# ESP-Light-Controller_2020-12-21_12-57-52.net
KiCad netlist of a schematic drawn in EasyEDA
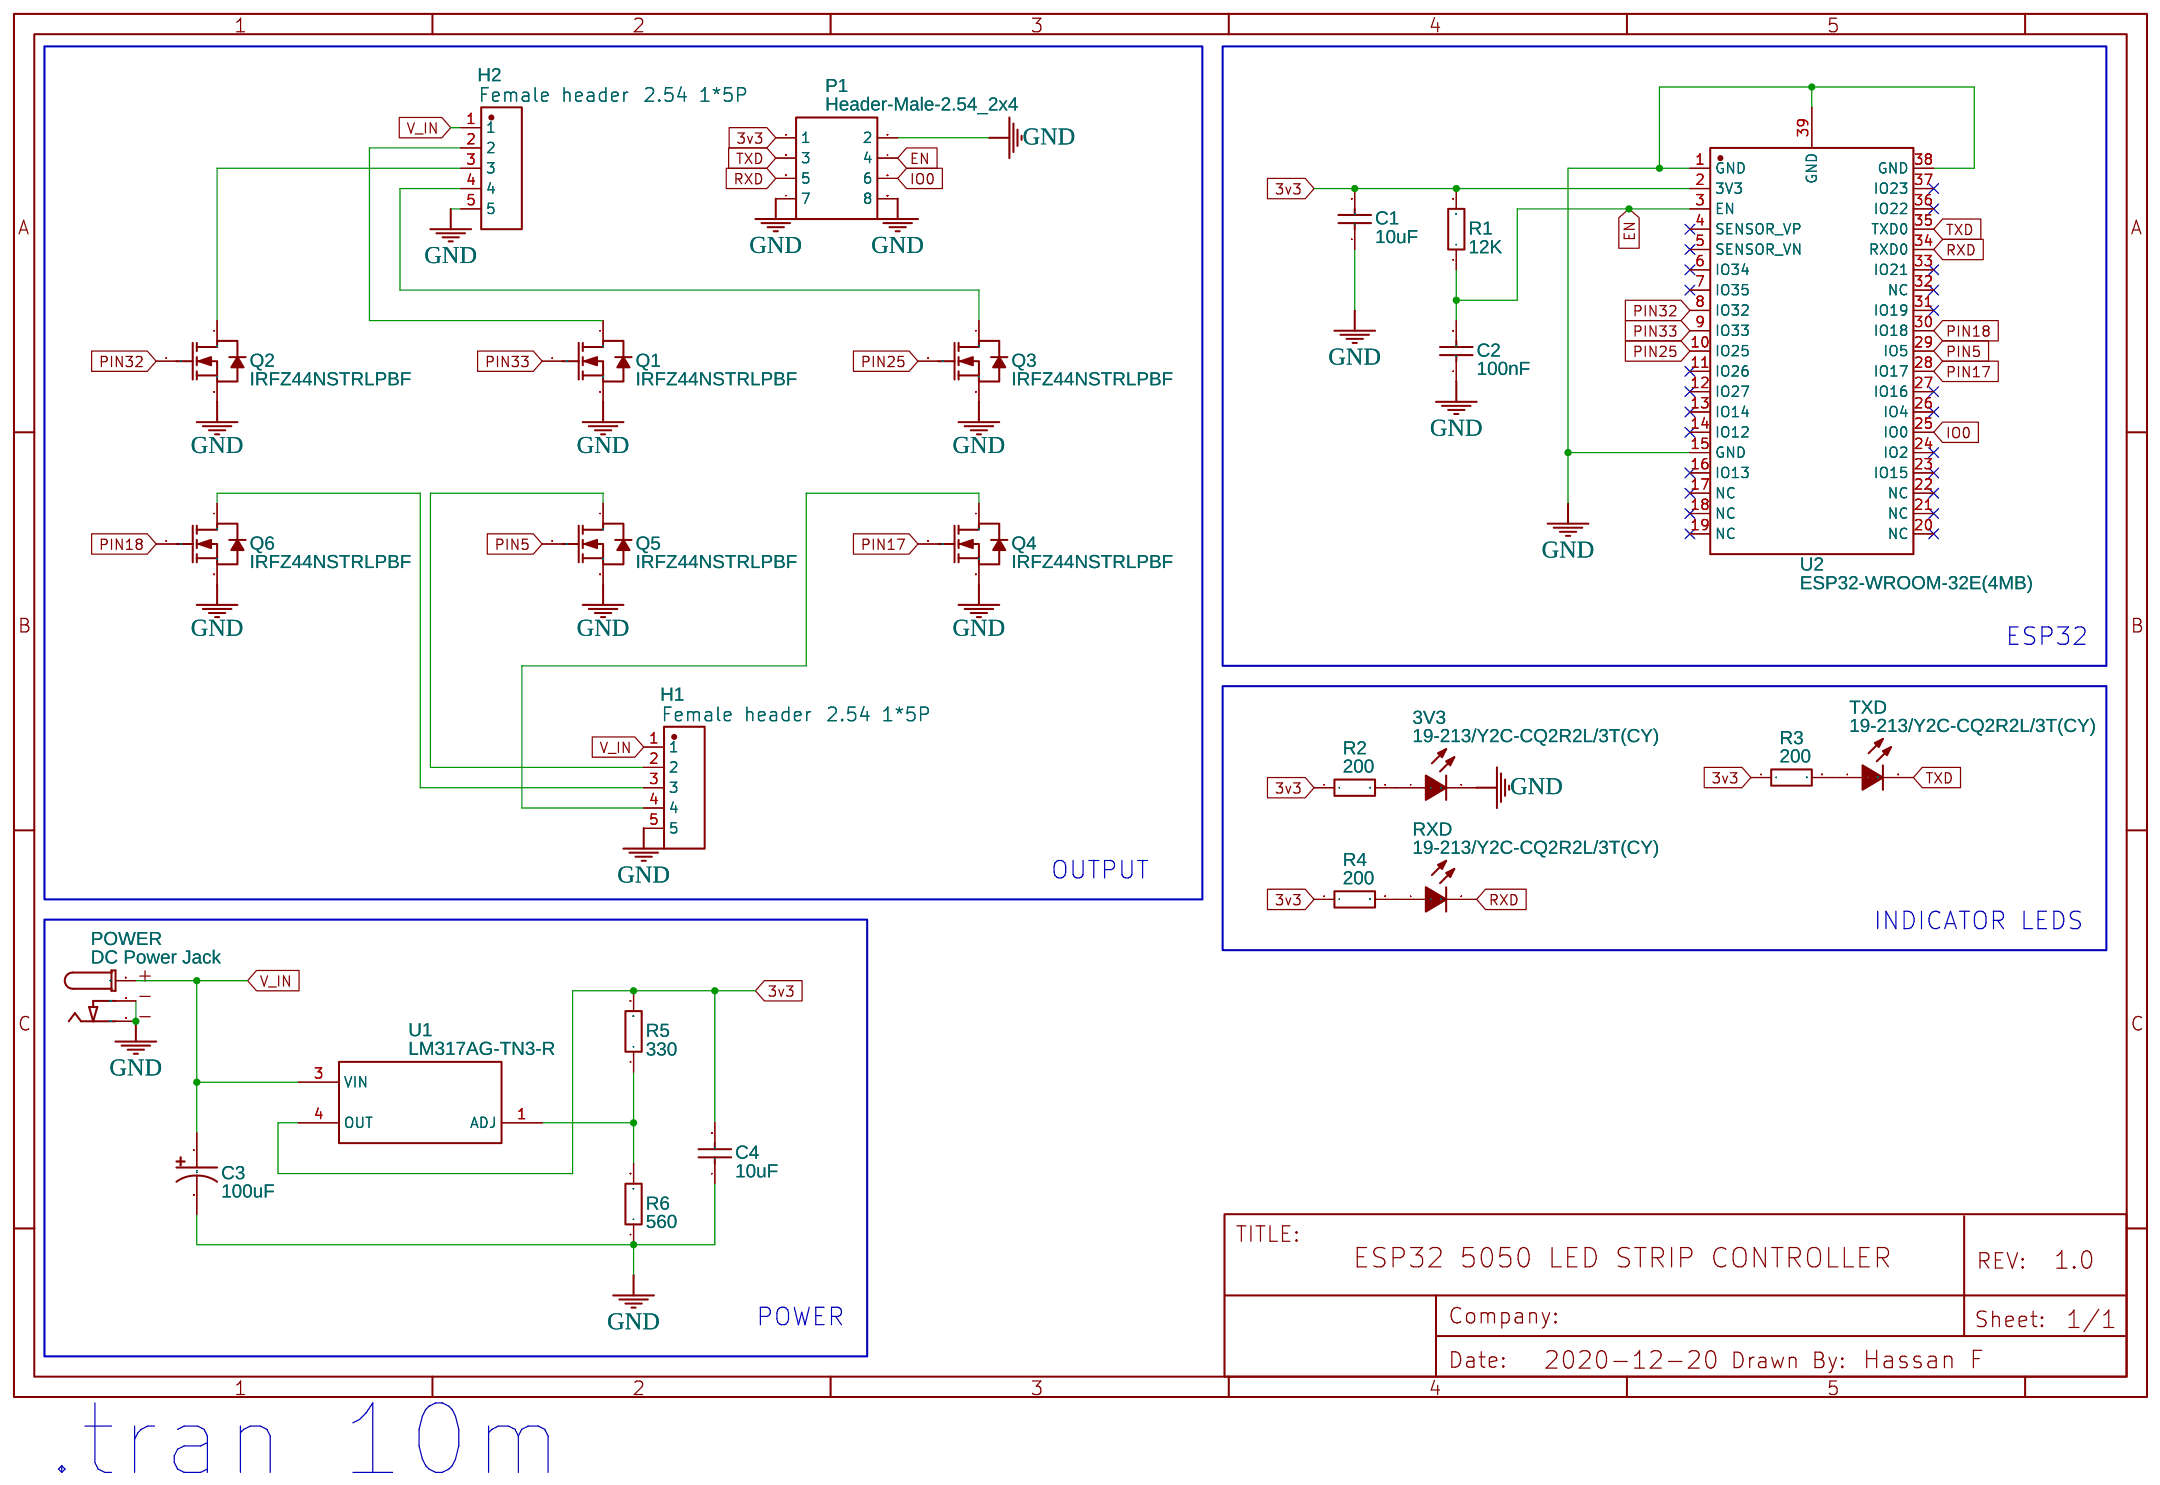
[diagram p0: schematic sheet]

(export (version "E")
  (design (tool "Eeschema 10.0.6"))
  (components
    (comp (ref "3V3")
      (value "19-213/Y2C-CQ2R2L/3T(CY)")
      (fields (field (name "BOM_Supplier Part") "C72038"))
      (libsource (lib "") (part "19-213/Y2C-CQ2R2L/3T(CY)_2"))
    )
    (comp (ref "C1")
      (value "10uF")
      (fields
        (field (name "BOM_Manufacturer Part") "CL05A106MQ5NUNC")
        (field (name "BOM_Supplier Part") "C15525")
      )
      (libsource (lib "") (part "CL05A106MQ5NUNC"))
    )
    (comp (ref "C2")
      (value "100nF")
      (fields
        (field (name "BOM_Manufacturer Part") "CL05B104KO5NNNC")
        (field (name "BOM_Supplier Part") "C1525")
      )
      (libsource (lib "") (part "CL05B104KO5NNNC"))
    )
    (comp (ref "C3")
      (value "100uF")
      (fields
        (field (name "BOM_Manufacturer Part") "EEEHA1C101WP")
        (field (name "BOM_Supplier Part") "C128466")
      )
      (libsource (lib "") (part "EEEHA1C101WP"))
    )
    (comp (ref "C4")
      (value "10uF")
      (fields
        (field (name "BOM_Manufacturer Part") "CL05A106MQ5NUNC")
        (field (name "BOM_Supplier Part") "C15525")
      )
      (libsource (lib "") (part "CL05A106MQ5NUNC"))
    )
    (comp (ref "H1")
      (value "Female header　2.54 1*5Ｐ")
      (fields (field (name "BOM_Supplier Part") "C46341"))
      (libsource (lib "") (part "Female header　2.54 1*5Ｐ"))
    )
    (comp (ref "H2")
      (value "Female header　2.54 1*5Ｐ")
      (fields (field (name "BOM_Supplier Part") "C46341"))
      (libsource (lib "") (part "Female header　2.54 1*5Ｐ"))
    )
    (comp (ref "P1")
      (value "Header-Male-2.54_2x4")
      (fields
        (field (name "BOM_Manufacturer Part") "Header2X4P 2.54mm")
        (field (name "BOM_Supplier Part") "C58363")
      )
      (libsource (lib "") (part "Header-Male-2.54_2x4"))
    )
    (comp (ref "POWER")
      (value "DC Power Jack")
      (fields
        (field (name "BOM_Manufacturer Part") "PJ-102AH")
        (field (name "BOM_Supplier Part") "CP-102AH-ND")
      )
      (libsource (lib "") (part "DC Power Jack"))
    )
    (comp (ref "Q1")
      (value "IRFZ44NSTRLPBF")
      (fields (field (name "BOM_Supplier Part") "C58228"))
      (libsource (lib "") (part "IRFZ44NSTRLPBF"))
    )
    (comp (ref "Q2")
      (value "IRFZ44NSTRLPBF")
      (fields (field (name "BOM_Supplier Part") "C58228"))
      (libsource (lib "") (part "IRFZ44NSTRLPBF"))
    )
    (comp (ref "Q3")
      (value "IRFZ44NSTRLPBF")
      (fields (field (name "BOM_Supplier Part") "C58228"))
      (libsource (lib "") (part "IRFZ44NSTRLPBF"))
    )
    (comp (ref "Q4")
      (value "IRFZ44NSTRLPBF")
      (fields (field (name "BOM_Supplier Part") "C58228"))
      (libsource (lib "") (part "IRFZ44NSTRLPBF"))
    )
    (comp (ref "Q5")
      (value "IRFZ44NSTRLPBF")
      (fields (field (name "BOM_Supplier Part") "C58228"))
      (libsource (lib "") (part "IRFZ44NSTRLPBF"))
    )
    (comp (ref "Q6")
      (value "IRFZ44NSTRLPBF")
      (fields (field (name "BOM_Supplier Part") "C58228"))
      (libsource (lib "") (part "IRFZ44NSTRLPBF"))
    )
    (comp (ref "R1")
      (value "12K")
      (fields
        (field (name "BOM_Manufacturer Part") "0402WGF1202TCE")
        (field (name "BOM_Supplier Part") "C25752")
      )
      (libsource (lib "") (part "0402WGF1202TCE"))
    )
    (comp (ref "R2")
      (value "200")
      (fields
        (field (name "BOM_Manufacturer Part") "0402WGF2000TCE")
        (field (name "BOM_Supplier Part") "C25087")
      )
      (libsource (lib "") (part "0402WGF2000TCE"))
    )
    (comp (ref "R3")
      (value "200")
      (fields
        (field (name "BOM_Manufacturer Part") "0402WGF2000TCE")
        (field (name "BOM_Supplier Part") "C25087")
      )
      (libsource (lib "") (part "0402WGF2000TCE"))
    )
    (comp (ref "R4")
      (value "200")
      (fields
        (field (name "BOM_Manufacturer Part") "0402WGF2000TCE")
        (field (name "BOM_Supplier Part") "C25087")
      )
      (libsource (lib "") (part "0402WGF2000TCE"))
    )
    (comp (ref "R5")
      (value "330")
      (fields
        (field (name "BOM_Manufacturer Part") "ERJP06F3300V")
        (field (name "BOM_Supplier Part") "C441977")
      )
      (libsource (lib "") (part "ERJP06F3300V"))
    )
    (comp (ref "R6")
      (value "560")
      (fields
        (field (name "BOM_Manufacturer Part") "ERJP06F5600V")
        (field (name "BOM_Supplier Part") "C441979")
      )
      (libsource (lib "") (part "ERJP06F5600V"))
    )
    (comp (ref "RXD")
      (value "19-213/Y2C-CQ2R2L/3T(CY)")
      (fields (field (name "BOM_Supplier Part") "C72038"))
      (libsource (lib "") (part "19-213/Y2C-CQ2R2L/3T(CY)_1"))
    )
    (comp (ref "TXD")
      (value "19-213/Y2C-CQ2R2L/3T(CY)")
      (fields (field (name "BOM_Supplier Part") "C72038"))
      (libsource (lib "") (part "19-213/Y2C-CQ2R2L/3T(CY)"))
    )
    (comp (ref "U1")
      (value "LM317AG-TN3-R")
      (fields (field (name "BOM_Supplier Part") "C75510"))
      (libsource (lib "") (part "LM317AG-TN3-R"))
    )
    (comp (ref "U2")
      (value "ESP32-WROOM-32E(4MB)")
      (fields (field (name "BOM_Supplier Part") "C701341"))
      (libsource (lib "") (part "ESP32-WROOM-32E(4MB)"))
    )
  )
  (nets
    (net (code "1") (name "3v3") (class "Default")
      (node (ref "C1") (pin "2") (pinfunction "2_2") (pintype "input"))
      (node (ref "C4") (pin "2") (pinfunction "2_2") (pintype "input"))
      (node (ref "P1") (pin "1") (pinfunction "1_1") (pintype "input"))
      (node (ref "R1") (pin "2") (pinfunction "2_2") (pintype "input"))
      (node (ref "R2") (pin "1") (pinfunction "1_1") (pintype "input"))
      (node (ref "R3") (pin "1") (pinfunction "1_1") (pintype "input"))
      (node (ref "R4") (pin "1") (pinfunction "1_1") (pintype "input"))
      (node (ref "R5") (pin "2") (pinfunction "2_2") (pintype "unspecified"))
      (node (ref "U1") (pin "4") (pinfunction "OUT_4") (pintype "unspecified"))
      (node (ref "U2") (pin "2") (pinfunction "3V3_2") (pintype "unspecified"))
    )
    (net (code "2") (name "EN") (class "Default")
      (node (ref "C2") (pin "2") (pinfunction "2_2") (pintype "input"))
      (node (ref "P1") (pin "4") (pinfunction "4_4") (pintype "input"))
      (node (ref "R1") (pin "1") (pinfunction "1_1") (pintype "input"))
      (node (ref "U2") (pin "3") (pinfunction "EN_3") (pintype "unspecified"))
    )
    (net (code "3") (name "GND") (class "Default")
      (node (ref "3V3") (pin "2") (pinfunction "C_2") (pintype "input"))
      (node (ref "C1") (pin "1") (pinfunction "1_1") (pintype "input"))
      (node (ref "C2") (pin "1") (pinfunction "1_1") (pintype "input"))
      (node (ref "C3") (pin "2") (pinfunction "2_2") (pintype "unspecified"))
      (node (ref "C4") (pin "1") (pinfunction "1_1") (pintype "input"))
      (node (ref "H1") (pin "5") (pinfunction "5_5") (pintype "unspecified"))
      (node (ref "H2") (pin "5") (pinfunction "5_5") (pintype "unspecified"))
      (node (ref "P1") (pin "2") (pinfunction "2_2") (pintype "input"))
      (node (ref "P1") (pin "7") (pinfunction "7_7") (pintype "input"))
      (node (ref "P1") (pin "8") (pinfunction "8_8") (pintype "input"))
      (node (ref "POWER") (pin "P2") (pinfunction "P2_P2") (pintype "unspecified"))
      (node (ref "POWER") (pin "P3") (pinfunction "P3_P3") (pintype "unspecified"))
      (node (ref "Q1") (pin "3") (pinfunction "S_3") (pintype "unspecified"))
      (node (ref "Q2") (pin "3") (pinfunction "S_3") (pintype "unspecified"))
      (node (ref "Q3") (pin "3") (pinfunction "S_3") (pintype "unspecified"))
      (node (ref "Q4") (pin "3") (pinfunction "S_3") (pintype "unspecified"))
      (node (ref "Q5") (pin "3") (pinfunction "S_3") (pintype "unspecified"))
      (node (ref "Q6") (pin "3") (pinfunction "S_3") (pintype "unspecified"))
      (node (ref "R6") (pin "1") (pinfunction "1_1") (pintype "unspecified"))
      (node (ref "U2") (pin "1") (pinfunction "GND_1") (pintype "unspecified"))
      (node (ref "U2") (pin "15") (pinfunction "GND_15") (pintype "unspecified"))
      (node (ref "U2") (pin "38") (pinfunction "GND_38") (pintype "unspecified"))
      (node (ref "U2") (pin "39") (pinfunction "GND_39") (pintype "unspecified"))
    )
    (net (code "4") (name "IO0") (class "Default")
      (node (ref "P1") (pin "6") (pinfunction "6_6") (pintype "input"))
      (node (ref "U2") (pin "25") (pinfunction "IO0_25") (pintype "unspecified"))
    )
    (net (code "5") (name "Net-(3V3-A)") (class "Default")
      (node (ref "3V3") (pin "1") (pinfunction "A_1") (pintype "input"))
      (node (ref "R2") (pin "2") (pinfunction "2_2") (pintype "input"))
    )
    (net (code "6") (name "Net-(Q1-D)") (class "Default")
      (node (ref "H2") (pin "2") (pinfunction "2_2") (pintype "unspecified"))
      (node (ref "Q1") (pin "4") (pinfunction "D_4") (pintype "unspecified"))
    )
    (net (code "7") (name "Net-(Q2-D)") (class "Default")
      (node (ref "H2") (pin "3") (pinfunction "3_3") (pintype "unspecified"))
      (node (ref "Q2") (pin "4") (pinfunction "D_4") (pintype "unspecified"))
    )
    (net (code "8") (name "Net-(Q3-D)") (class "Default")
      (node (ref "H2") (pin "4") (pinfunction "4_4") (pintype "unspecified"))
      (node (ref "Q3") (pin "4") (pinfunction "D_4") (pintype "unspecified"))
    )
    (net (code "9") (name "Net-(Q4-D)") (class "Default")
      (node (ref "H1") (pin "4") (pinfunction "4_4") (pintype "unspecified"))
      (node (ref "Q4") (pin "4") (pinfunction "D_4") (pintype "unspecified"))
    )
    (net (code "10") (name "Net-(Q5-D)") (class "Default")
      (node (ref "H1") (pin "2") (pinfunction "2_2") (pintype "unspecified"))
      (node (ref "Q5") (pin "4") (pinfunction "D_4") (pintype "unspecified"))
    )
    (net (code "11") (name "Net-(Q6-D)") (class "Default")
      (node (ref "H1") (pin "3") (pinfunction "3_3") (pintype "unspecified"))
      (node (ref "Q6") (pin "4") (pinfunction "D_4") (pintype "unspecified"))
    )
    (net (code "12") (name "Net-(RXD-A)") (class "Default")
      (node (ref "R4") (pin "2") (pinfunction "2_2") (pintype "input"))
      (node (ref "RXD") (pin "1") (pinfunction "A_1") (pintype "input"))
    )
    (net (code "13") (name "Net-(TXD-A)") (class "Default")
      (node (ref "R3") (pin "2") (pinfunction "2_2") (pintype "input"))
      (node (ref "TXD") (pin "1") (pinfunction "A_1") (pintype "input"))
    )
    (net (code "14") (name "Net-(U1-ADJ)") (class "Default")
      (node (ref "R5") (pin "1") (pinfunction "1_1") (pintype "unspecified"))
      (node (ref "R6") (pin "2") (pinfunction "2_2") (pintype "unspecified"))
      (node (ref "U1") (pin "1") (pinfunction "ADJ_1") (pintype "unspecified"))
    )
    (net (code "15") (name "PIN5") (class "Default")
      (node (ref "Q5") (pin "1") (pinfunction "G_1") (pintype "unspecified"))
      (node (ref "U2") (pin "29") (pinfunction "IO5_29") (pintype "unspecified"))
    )
    (net (code "16") (name "PIN17") (class "Default")
      (node (ref "Q4") (pin "1") (pinfunction "G_1") (pintype "unspecified"))
      (node (ref "U2") (pin "28") (pinfunction "IO17_28") (pintype "unspecified"))
    )
    (net (code "17") (name "PIN18") (class "Default")
      (node (ref "Q6") (pin "1") (pinfunction "G_1") (pintype "unspecified"))
      (node (ref "U2") (pin "30") (pinfunction "IO18_30") (pintype "unspecified"))
    )
    (net (code "18") (name "PIN25") (class "Default")
      (node (ref "Q3") (pin "1") (pinfunction "G_1") (pintype "unspecified"))
      (node (ref "U2") (pin "10") (pinfunction "IO25_10") (pintype "unspecified"))
    )
    (net (code "19") (name "PIN32") (class "Default")
      (node (ref "Q2") (pin "1") (pinfunction "G_1") (pintype "unspecified"))
      (node (ref "U2") (pin "8") (pinfunction "IO32_8") (pintype "unspecified"))
    )
    (net (code "20") (name "PIN33") (class "Default")
      (node (ref "Q1") (pin "1") (pinfunction "G_1") (pintype "unspecified"))
      (node (ref "U2") (pin "9") (pinfunction "IO33_9") (pintype "unspecified"))
    )
    (net (code "21") (name "RXD") (class "Default")
      (node (ref "P1") (pin "5") (pinfunction "5_5") (pintype "input"))
      (node (ref "RXD") (pin "2") (pinfunction "C_2") (pintype "input"))
      (node (ref "U2") (pin "34") (pinfunction "RXD0_34") (pintype "unspecified"))
    )
    (net (code "22") (name "TXD") (class "Default")
      (node (ref "P1") (pin "3") (pinfunction "3_3") (pintype "input"))
      (node (ref "TXD") (pin "2") (pinfunction "C_2") (pintype "input"))
      (node (ref "U2") (pin "35") (pinfunction "TXD0_35") (pintype "unspecified"))
    )
    (net (code "23") (name "V_IN") (class "Default")
      (node (ref "C3") (pin "1") (pinfunction "1_1") (pintype "unspecified"))
      (node (ref "H1") (pin "1") (pinfunction "1_1") (pintype "unspecified"))
      (node (ref "H2") (pin "1") (pinfunction "1_1") (pintype "unspecified"))
      (node (ref "POWER") (pin "P1") (pinfunction "P1_P1") (pintype "unspecified"))
      (node (ref "U1") (pin "3") (pinfunction "VIN_3") (pintype "unspecified"))
    )
    (net (code "24") (name "unconnected-(U2-IO2-Pad24)") (class "Default")
      (node (ref "U2") (pin "24") (pinfunction "IO2_24") (pintype "unspecified+no_connect"))
    )
    (net (code "25") (name "unconnected-(U2-IO4-Pad26)") (class "Default")
      (node (ref "U2") (pin "26") (pinfunction "IO4_26") (pintype "unspecified+no_connect"))
    )
    (net (code "26") (name "unconnected-(U2-IO12-Pad14)") (class "Default")
      (node (ref "U2") (pin "14") (pinfunction "IO12_14") (pintype "unspecified+no_connect"))
    )
    (net (code "27") (name "unconnected-(U2-IO13-Pad16)") (class "Default")
      (node (ref "U2") (pin "16") (pinfunction "IO13_16") (pintype "unspecified+no_connect"))
    )
    (net (code "28") (name "unconnected-(U2-IO14-Pad13)") (class "Default")
      (node (ref "U2") (pin "13") (pinfunction "IO14_13") (pintype "unspecified+no_connect"))
    )
    (net (code "29") (name "unconnected-(U2-IO15-Pad23)") (class "Default")
      (node (ref "U2") (pin "23") (pinfunction "IO15_23") (pintype "unspecified+no_connect"))
    )
    (net (code "30") (name "unconnected-(U2-IO16-Pad27)") (class "Default")
      (node (ref "U2") (pin "27") (pinfunction "IO16_27") (pintype "unspecified+no_connect"))
    )
    (net (code "31") (name "unconnected-(U2-IO19-Pad31)") (class "Default")
      (node (ref "U2") (pin "31") (pinfunction "IO19_31") (pintype "unspecified+no_connect"))
    )
    (net (code "32") (name "unconnected-(U2-IO21-Pad33)") (class "Default")
      (node (ref "U2") (pin "33") (pinfunction "IO21_33") (pintype "unspecified+no_connect"))
    )
    (net (code "33") (name "unconnected-(U2-IO22-Pad36)") (class "Default")
      (node (ref "U2") (pin "36") (pinfunction "IO22_36") (pintype "unspecified+no_connect"))
    )
    (net (code "34") (name "unconnected-(U2-IO23-Pad37)") (class "Default")
      (node (ref "U2") (pin "37") (pinfunction "IO23_37") (pintype "unspecified+no_connect"))
    )
    (net (code "35") (name "unconnected-(U2-IO26-Pad11)") (class "Default")
      (node (ref "U2") (pin "11") (pinfunction "IO26_11") (pintype "unspecified+no_connect"))
    )
    (net (code "36") (name "unconnected-(U2-IO27-Pad12)") (class "Default")
      (node (ref "U2") (pin "12") (pinfunction "IO27_12") (pintype "unspecified+no_connect"))
    )
    (net (code "37") (name "unconnected-(U2-IO34-Pad6)") (class "Default")
      (node (ref "U2") (pin "6") (pinfunction "IO34_6") (pintype "unspecified+no_connect"))
    )
    (net (code "38") (name "unconnected-(U2-IO35-Pad7)") (class "Default")
      (node (ref "U2") (pin "7") (pinfunction "IO35_7") (pintype "unspecified+no_connect"))
    )
    (net (code "39") (name "unconnected-(U2-NC-Pad17)") (class "Default")
      (node (ref "U2") (pin "17") (pinfunction "NC_17") (pintype "unspecified+no_connect"))
    )
    (net (code "40") (name "unconnected-(U2-NC-Pad18)") (class "Default")
      (node (ref "U2") (pin "18") (pinfunction "NC_18") (pintype "unspecified+no_connect"))
    )
    (net (code "41") (name "unconnected-(U2-NC-Pad19)") (class "Default")
      (node (ref "U2") (pin "19") (pinfunction "NC_19") (pintype "unspecified+no_connect"))
    )
    (net (code "42") (name "unconnected-(U2-NC-Pad20)") (class "Default")
      (node (ref "U2") (pin "20") (pinfunction "NC_20") (pintype "unspecified+no_connect"))
    )
    (net (code "43") (name "unconnected-(U2-NC-Pad21)") (class "Default")
      (node (ref "U2") (pin "21") (pinfunction "NC_21") (pintype "unspecified+no_connect"))
    )
    (net (code "44") (name "unconnected-(U2-NC-Pad22)") (class "Default")
      (node (ref "U2") (pin "22") (pinfunction "NC_22") (pintype "unspecified+no_connect"))
    )
    (net (code "45") (name "unconnected-(U2-NC-Pad32)") (class "Default")
      (node (ref "U2") (pin "32") (pinfunction "NC_32") (pintype "unspecified+no_connect"))
    )
    (net (code "46") (name "unconnected-(U2-SENSOR_VN-Pad5)") (class "Default")
      (node (ref "U2") (pin "5") (pinfunction "SENSOR_VN_5") (pintype "unspecified+no_connect"))
    )
    (net (code "47") (name "unconnected-(U2-SENSOR_VP-Pad4)") (class "Default")
      (node (ref "U2") (pin "4") (pinfunction "SENSOR_VP_4") (pintype "unspecified+no_connect"))
    )
  )
)
